# MCU.net
KiCad netlist of a schematic drawn in Altium Designer
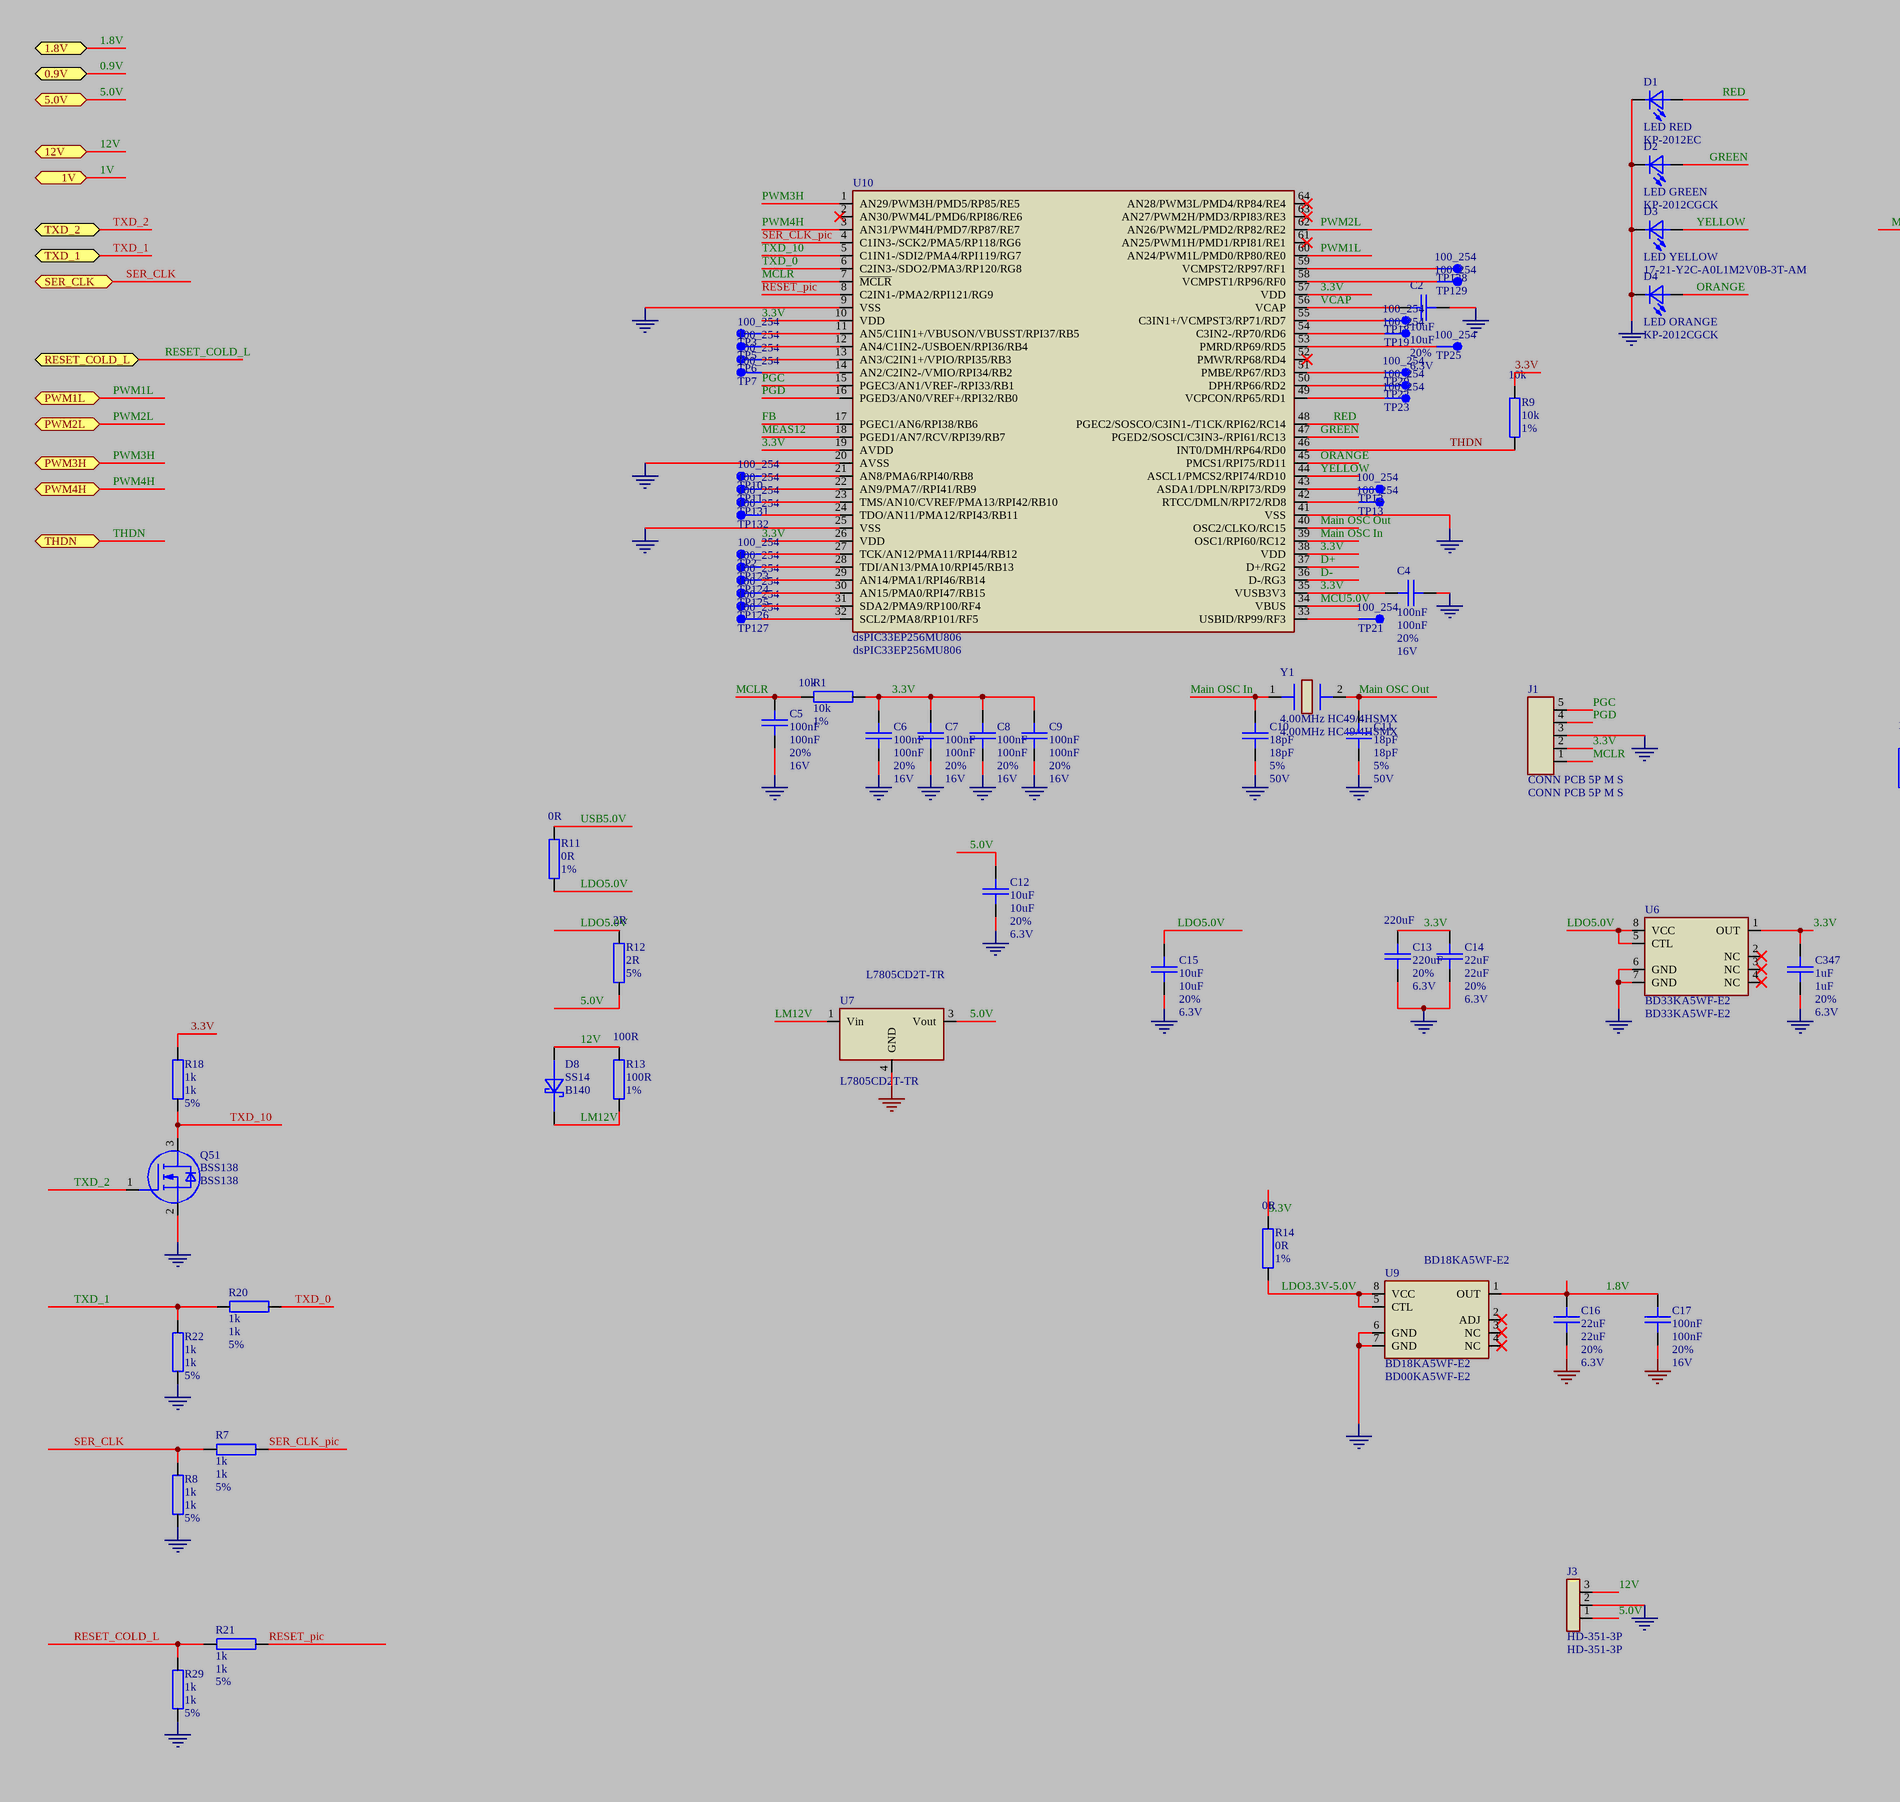
[diagram p0: MCU.SchDoc, left]
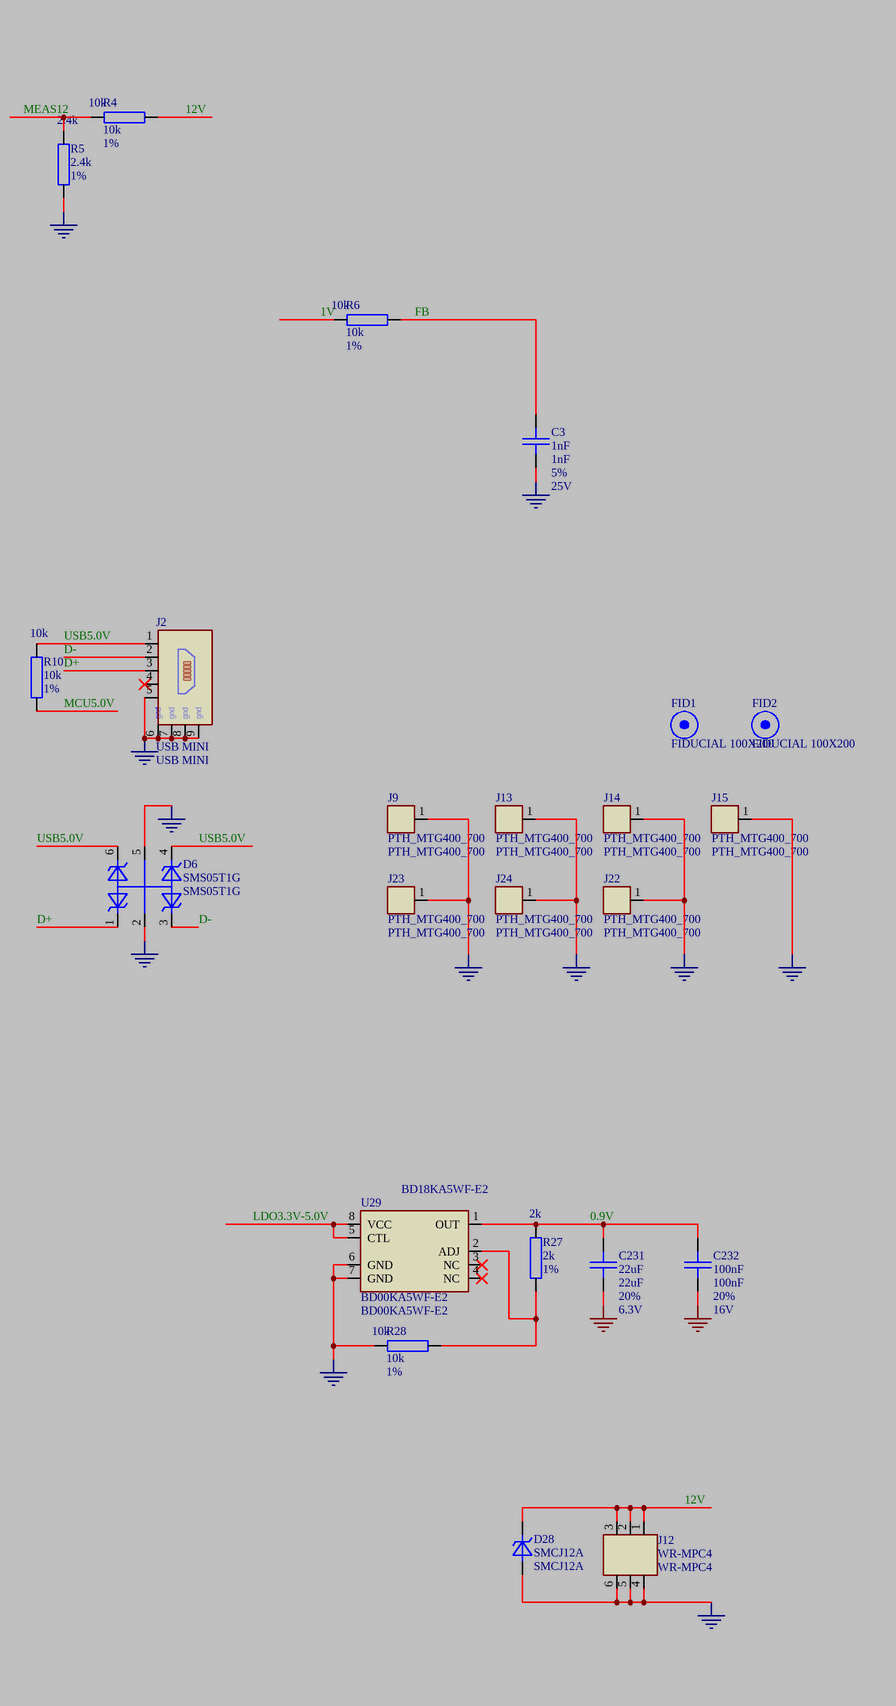
[diagram p1: MCU.SchDoc, right]

(export (version "E")
  (design (tool "Eeschema 10.0.6"))
  (components
    (comp (ref "C2")
      (value "10uF")
      (footprint "SMD_0603_CAPC1608X95N")
      (fields
        (field (name "DB_PART_NUMBER") "CAP000043646")
        (field (name "DB_VALUE") "10uF")
        (field (name "DB_TOLERANCE") "20%")
        (field (name "DB_VOLTAGE") "6.3V")
        (field (name "DB_MANUFACTURER_PART") "KEMET    C0603C106M9PAC")
        (field (name "DB_APPROVED_BY") "ISHIDDEN=T")
      )
      (libsource (lib "Database_Libs1") (part "C"))
    )
    (comp (ref "C3")
      (value "1nF")
      (footprint "SMD_0603_CAPC1608X95N")
      (fields
        (field (name "DB_PART_NUMBER") "CAP000024113")
        (field (name "DB_VALUE") "1nF")
        (field (name "DB_TOLERANCE") "5%")
        (field (name "DB_VOLTAGE") "25V")
        (field (name "DB_MANUFACTURER_PART") "KEMET    C0603C102J3RAC")
        (field (name "DB_APPROVED_BY") "ISHIDDEN=T")
      )
      (libsource (lib "Database_Libs1") (part "C"))
    )
    (comp (ref "C4")
      (value "100nF")
      (footprint "SMD_0402_CAPC1005X55N")
      (fields
        (field (name "DB_PART_NUMBER") "CAP000022751")
        (field (name "DB_VALUE") "100nF")
        (field (name "DB_TOLERANCE") "20%")
        (field (name "DB_VOLTAGE") "16V")
        (field (name "DB_MANUFACTURER_PART") "KEMET    C0402F104M4RAC")
        (field (name "DB_APPROVED_BY") "ISHIDDEN=T")
      )
      (libsource (lib "Database_Libs1") (part "C"))
    )
    (comp (ref "C5")
      (value "100nF")
      (footprint "SMD_0402_CAPC1005X55N")
      (fields
        (field (name "DB_PART_NUMBER") "CAP000022751")
        (field (name "DB_VALUE") "100nF")
        (field (name "DB_TOLERANCE") "20%")
        (field (name "DB_VOLTAGE") "16V")
        (field (name "DB_MANUFACTURER_PART") "KEMET    C0402F104M4RAC")
        (field (name "DB_APPROVED_BY") "ISHIDDEN=T")
      )
      (libsource (lib "Database_Libs1") (part "C"))
    )
    (comp (ref "C6")
      (value "100nF")
      (footprint "SMD_0402_CAPC1005X55N")
      (fields
        (field (name "DB_PART_NUMBER") "CAP000022751")
        (field (name "DB_VALUE") "100nF")
        (field (name "DB_TOLERANCE") "20%")
        (field (name "DB_VOLTAGE") "16V")
        (field (name "DB_MANUFACTURER_PART") "KEMET    C0402F104M4RAC")
        (field (name "DB_APPROVED_BY") "ISHIDDEN=T")
      )
      (libsource (lib "Database_Libs1") (part "C"))
    )
    (comp (ref "C7")
      (value "100nF")
      (footprint "SMD_0402_CAPC1005X55N")
      (fields
        (field (name "DB_PART_NUMBER") "CAP000022751")
        (field (name "DB_VALUE") "100nF")
        (field (name "DB_TOLERANCE") "20%")
        (field (name "DB_VOLTAGE") "16V")
        (field (name "DB_MANUFACTURER_PART") "KEMET    C0402F104M4RAC")
        (field (name "DB_APPROVED_BY") "ISHIDDEN=T")
      )
      (libsource (lib "Database_Libs1") (part "C"))
    )
    (comp (ref "C8")
      (value "100nF")
      (footprint "SMD_0402_CAPC1005X55N")
      (fields
        (field (name "DB_PART_NUMBER") "CAP000022751")
        (field (name "DB_VALUE") "100nF")
        (field (name "DB_TOLERANCE") "20%")
        (field (name "DB_VOLTAGE") "16V")
        (field (name "DB_MANUFACTURER_PART") "KEMET    C0402F104M4RAC")
        (field (name "DB_APPROVED_BY") "ISHIDDEN=T")
      )
      (libsource (lib "Database_Libs1") (part "C"))
    )
    (comp (ref "C9")
      (value "100nF")
      (footprint "SMD_0402_CAPC1005X55N")
      (fields
        (field (name "DB_PART_NUMBER") "CAP000022751")
        (field (name "DB_VALUE") "100nF")
        (field (name "DB_TOLERANCE") "20%")
        (field (name "DB_VOLTAGE") "16V")
        (field (name "DB_MANUFACTURER_PART") "KEMET    C0402F104M4RAC")
        (field (name "DB_APPROVED_BY") "ISHIDDEN=T")
      )
      (libsource (lib "Database_Libs1") (part "C"))
    )
    (comp (ref "C10")
      (value "18pF")
      (footprint "SMD_0603_CAPC1608X95N")
      (fields
        (field (name "DB_PART_NUMBER") "CAP000031922")
        (field (name "DB_VALUE") "18pF")
        (field (name "DB_TOLERANCE") "5%")
        (field (name "DB_VOLTAGE") "50V")
        (field (name "DB_MANUFACTURER_PART") "KEMET    C0603C180J5GAC")
        (field (name "DB_APPROVED_BY") "ISHIDDEN=T")
      )
      (libsource (lib "Database_Libs1") (part "C"))
    )
    (comp (ref "C11")
      (value "18pF")
      (footprint "SMD_0603_CAPC1608X95N")
      (fields
        (field (name "DB_PART_NUMBER") "CAP000031922")
        (field (name "DB_VALUE") "18pF")
        (field (name "DB_TOLERANCE") "5%")
        (field (name "DB_VOLTAGE") "50V")
        (field (name "DB_MANUFACTURER_PART") "KEMET    C0603C180J5GAC")
        (field (name "DB_APPROVED_BY") "ISHIDDEN=T")
      )
      (libsource (lib "Database_Libs1") (part "C"))
    )
    (comp (ref "C12")
      (value "10uF")
      (footprint "SMD_0603_CAPC1608X95N")
      (fields
        (field (name "DB_PART_NUMBER") "CAP000043646")
        (field (name "DB_VALUE") "10uF")
        (field (name "DB_TOLERANCE") "20%")
        (field (name "DB_VOLTAGE") "6.3V")
        (field (name "DB_MANUFACTURER_PART") "KEMET    C0603C106M9PAC")
        (field (name "DB_APPROVED_BY") "ISHIDDEN=T")
      )
      (libsource (lib "Database_Libs1") (part "C"))
    )
    (comp (ref "C13")
      (value "220uF")
      (footprint "SMD_1210_CAPC3225X279N")
      (fields
        (field (name "DB_PART_NUMBER") "CAP000047355")
        (field (name "DB_VALUE") "220uF")
        (field (name "DB_TOLERANCE") "20%")
        (field (name "DB_VOLTAGE") "6.3V")
        (field (name "DB_MANUFACTURER_PART") "SAMSUNG    CL32A227MQVNNNE")
        (field (name "DB_APPROVED_BY") "VSN")
      )
      (libsource (lib "Database_Libs1") (part "C"))
    )
    (comp (ref "C14")
      (value "22uF")
      (footprint "SMD_0805_CAPC2012X145N")
      (fields
        (field (name "DB_PART_NUMBER") "CAP000043686")
        (field (name "DB_VALUE") "22uF")
        (field (name "DB_TOLERANCE") "20%")
        (field (name "DB_VOLTAGE") "6.3V")
        (field (name "DB_MANUFACTURER_PART") "KEMET    C0805C226M9PAC")
        (field (name "DB_APPROVED_BY") "ISHIDDEN=T")
      )
      (libsource (lib "Database_Libs1") (part "C"))
    )
    (comp (ref "C15")
      (value "10uF")
      (footprint "SMD_0603_CAPC1608X95N")
      (fields
        (field (name "DB_PART_NUMBER") "CAP000043646")
        (field (name "DB_VALUE") "10uF")
        (field (name "DB_TOLERANCE") "20%")
        (field (name "DB_VOLTAGE") "6.3V")
        (field (name "DB_MANUFACTURER_PART") "KEMET    C0603C106M9PAC")
        (field (name "DB_APPROVED_BY") "ISHIDDEN=T")
      )
      (libsource (lib "Database_Libs1") (part "C"))
    )
    (comp (ref "C16")
      (value "22uF")
      (footprint "SMD_0805_CAPC2012X145N")
      (fields
        (field (name "DB_PART_NUMBER") "CAP000043686")
        (field (name "DB_VALUE") "22uF")
        (field (name "DB_TOLERANCE") "20%")
        (field (name "DB_VOLTAGE") "6.3V")
        (field (name "DB_MANUFACTURER_PART") "KEMET    C0805C226M9PAC")
        (field (name "DB_APPROVED_BY") "ISHIDDEN=T")
      )
      (libsource (lib "Database_Libs1") (part "C"))
    )
    (comp (ref "C17")
      (value "100nF")
      (footprint "SMD_0402_CAPC1005X55N")
      (fields
        (field (name "DB_PART_NUMBER") "CAP000022751")
        (field (name "DB_VALUE") "100nF")
        (field (name "DB_TOLERANCE") "20%")
        (field (name "DB_VOLTAGE") "16V")
        (field (name "DB_MANUFACTURER_PART") "KEMET    C0402F104M4RAC")
        (field (name "DB_APPROVED_BY") "ISHIDDEN=T")
      )
      (libsource (lib "Database_Libs1") (part "C"))
    )
    (comp (ref "C231")
      (value "22uF")
      (footprint "SMD_0805_CAPC2012X145N")
      (fields
        (field (name "DB_PART_NUMBER") "CAP000043686")
        (field (name "DB_VALUE") "22uF")
        (field (name "DB_TOLERANCE") "20%")
        (field (name "DB_VOLTAGE") "6.3V")
        (field (name "DB_MANUFACTURER_PART") "KEMET    C0805C226M9PAC")
        (field (name "DB_APPROVED_BY") "ISHIDDEN=T")
      )
      (libsource (lib "Database_Libs1") (part "C"))
    )
    (comp (ref "C232")
      (value "100nF")
      (footprint "SMD_0402_CAPC1005X55N")
      (fields
        (field (name "DB_PART_NUMBER") "CAP000022751")
        (field (name "DB_VALUE") "100nF")
        (field (name "DB_TOLERANCE") "20%")
        (field (name "DB_VOLTAGE") "16V")
        (field (name "DB_MANUFACTURER_PART") "KEMET    C0402F104M4RAC")
        (field (name "DB_APPROVED_BY") "ISHIDDEN=T")
      )
      (libsource (lib "Database_Libs1") (part "C"))
    )
    (comp (ref "C347")
      (value "1uF")
      (footprint "SMD_0603_CAPC1608X95N")
      (fields
        (field (name "DB_PART_NUMBER") "CAP000043344")
        (field (name "DB_VALUE") "1uF")
        (field (name "DB_TOLERANCE") "20%")
        (field (name "DB_VOLTAGE") "6.3V")
        (field (name "DB_MANUFACTURER_PART") "KEMET    C0603C105M9PAC")
        (field (name "DB_APPROVED_BY") "ISHIDDEN=T")
      )
      (libsource (lib "Database_Libs1") (part "C"))
    )
    (comp (ref "D1")
      (value "LED RED")
      (footprint "SMD_0805_LED2012X100N")
      (fields
        (field (name "DB_PART_NUMBER") "OPT000000095")
        (field (name "DB_VALUE") "KP-2012EC")
        (field (name "DB_MANUFACTURER_PART") "KINGBRIGHT       KP-2012EC")
        (field (name "DB_APPROVED_BY") "VSN")
      )
      (libsource (lib "Database_Libs1") (part "LED"))
    )
    (comp (ref "D2")
      (value "LED GREEN")
      (footprint "SMD_0805_LED2012X100N")
      (fields
        (field (name "DB_PART_NUMBER") "OPT000000096")
        (field (name "DB_VALUE") "KP-2012CGCK")
        (field (name "DB_MANUFACTURER_PART") "KINGBRIGHT       KP-2012CGCK")
        (field (name "DB_APPROVED_BY") "VSN")
      )
      (libsource (lib "Database_Libs1") (part "LED"))
    )
    (comp (ref "D3")
      (value "LED YELLOW")
      (footprint "SMD_0805_LED2012X100N")
      (fields
        (field (name "DB_PART_NUMBER") "OPT000000092")
        (field (name "DB_VALUE") "17-21-Y2C-A0L1M2V0B-3T-AM")
        (field (name "DB_MANUFACTURER_PART") "EVERLIGHT       17-21-Y2C-A0L1M2V0B-3T-AM")
        (field (name "DB_APPROVED_BY") "VSN")
      )
      (libsource (lib "Database_Libs1") (part "LED"))
    )
    (comp (ref "D4")
      (value "LED ORANGE")
      (footprint "SMD_0805_LED2012X100N")
      (fields
        (field (name "DB_PART_NUMBER") "OPT0000000zz")
        (field (name "DB_VALUE") "KP-2012CGCK")
        (field (name "DB_MANUFACTURER_PART") "KINGBRIGHT       KP-2012CGCK")
        (field (name "DB_APPROVED_BY") "VSN")
      )
      (libsource (lib "Database_Libs1") (part "LED"))
    )
    (comp (ref "D6")
      (value "SMS05T1G")
      (footprint "SMD_SOT457_SOT95P275X110-6N")
      (fields
        (field (name "DB_PART_NUMBER") "DDE000002846")
        (field (name "DB_VALUE") "SMS05T1G")
        (field (name "DB_MANUFACTURER_PART") "ON SEMICONDUCTOR        SMS05T1G")
        (field (name "DB_APPROVED_BY") "VSN")
      )
      (libsource (lib "Database_Libs1") (part "D_TVS_QUAD_C1A2C3C4A5C6"))
    )
    (comp (ref "D8")
      (value "SS14")
      (footprint "SMD_DO214AC_SMA")
      (fields
        (field (name "DB_PART_NUMBER") "DDE000000580")
        (field (name "DB_VALUE") "B140")
        (field (name "DB_MANUFACTURER_PART") "Diodes        B140")
        (field (name "DB_APPROVED_BY") "ISHIDDEN=T")
      )
      (libsource (lib "Database_Libs1") (part "D_STKY"))
    )
    (comp (ref "D28")
      (value "SMCJ12A")
      (footprint "SMD_DO214AC_SMC")
      (fields
        (field (name "DB_PART_NUMBER") "DDE000001725")
        (field (name "DB_VALUE") "SMCJ12A")
        (field (name "DB_MANUFACTURER_PART") "Diodes        SMCJ12A")
        (field (name "DB_APPROVED_BY") "ISHIDDEN=T")
      )
      (libsource (lib "Database_Libs1") (part "D_TVS_UNI"))
    )
    (comp (ref "FID1")
      (value "FIDUCIAL 100X200")
      (footprint "FID100X200")
      (fields
        (field (name "DB_PART_NUMBER") "FID000000001")
        (field (name "DB_MANUFACTURER_PART") "ISHIDDEN=T")
        (field (name "DB_APPROVED_BY") "ISHIDDEN=T")
      )
      (libsource (lib "Database_Libs1") (part "FIDUCIAL"))
    )
    (comp (ref "FID2")
      (value "FIDUCIAL 100X200")
      (footprint "FID100X200")
      (fields
        (field (name "DB_PART_NUMBER") "FID000000001")
        (field (name "DB_MANUFACTURER_PART") "ISHIDDEN=T")
        (field (name "DB_APPROVED_BY") "ISHIDDEN=T")
      )
      (libsource (lib "Database_Libs1") (part "FIDUCIAL"))
    )
    (comp (ref "J1")
      (value "CONN PCB 5P M S")
      (footprint "PTH_HDRV05W64P254_1X05")
      (fields
        (field (name "DB_PART_NUMBER") "CON000000006")
        (field (name "DB_VALUE") "CONN PCB 5P M S")
        (field (name "DB_MANUFACTURER_PART") "W+P        143-12-005-00")
        (field (name "DB_APPROVED_BY") "VSN")
      )
      (libsource (lib "Database_Libs1") (part "CON_5PINS"))
    )
    (comp (ref "J2")
      (value "USB MINI")
      (footprint "SMD_CON-CVILUX-CU04-SCM15B0")
      (fields
        (field (name "DB_PART_NUMBER") "CON000000048")
        (field (name "DB_VALUE") "USB MINI")
        (field (name "DB_MANUFACTURER_PART") "CVILUX       CU04-SCM15B0-R0-LF")
        (field (name "DB_APPROVED_BY") "VSN")
      )
      (libsource (lib "Database_Libs1") (part "CON_USB_MINI_1"))
    )
    (comp (ref "J3")
      (value "HD-351-3P")
      (footprint "PTH_CON_HD-351-3P")
      (fields
        (field (name "DB_PART_NUMBER") "CON000000272")
        (field (name "DB_VALUE") "HD-351-3P")
        (field (name "DB_MANUFACTURER_PART") "HOW DER      HD-351-3P")
        (field (name "DB_APPROVED_BY") "VSN")
      )
      (libsource (lib "Database_Libs1") (part "CON_3PINS"))
    )
    (comp (ref "J9")
      (value "PTH_MTG400_700")
      (footprint "PTH_MTG400_700")
      (fields
        (field (name "DB_PART_NUMBER") "MTH000000030")
        (field (name "DB_VALUE") "PTH_MTG400_700")
        (field (name "DB_APPROVED_BY") "VSN")
      )
      (libsource (lib "Database_Libs1") (part "CON_1PIN"))
    )
    (comp (ref "J12")
      (value "WR-MPC4")
      (footprint "PTH_CON_WR-MRC4-6P_S")
      (fields
        (field (name "DB_PART_NUMBER") "CON000000279")
        (field (name "DB_VALUE") "WR-MPC4")
        (field (name "DB_MANUFACTURER_PART") "WE        	649 006 211 22")
        (field (name "DB_APPROVED_BY") "VSN")
      )
      (libsource (lib "Database_Libs1") (part "CON_2ROWS_6PINS_1"))
    )
    (comp (ref "J13")
      (value "PTH_MTG400_700")
      (footprint "PTH_MTG400_700")
      (fields
        (field (name "DB_PART_NUMBER") "MTH000000030")
        (field (name "DB_VALUE") "PTH_MTG400_700")
        (field (name "DB_APPROVED_BY") "VSN")
      )
      (libsource (lib "Database_Libs1") (part "CON_1PIN"))
    )
    (comp (ref "J14")
      (value "PTH_MTG400_700")
      (footprint "PTH_MTG400_700")
      (fields
        (field (name "DB_PART_NUMBER") "MTH000000030")
        (field (name "DB_VALUE") "PTH_MTG400_700")
        (field (name "DB_APPROVED_BY") "VSN")
      )
      (libsource (lib "Database_Libs1") (part "CON_1PIN"))
    )
    (comp (ref "J15")
      (value "PTH_MTG400_700")
      (footprint "PTH_MTG400_700")
      (fields
        (field (name "DB_PART_NUMBER") "MTH000000030")
        (field (name "DB_VALUE") "PTH_MTG400_700")
        (field (name "DB_APPROVED_BY") "VSN")
      )
      (libsource (lib "Database_Libs1") (part "CON_1PIN"))
    )
    (comp (ref "J22")
      (value "PTH_MTG400_700")
      (footprint "PTH_MTG400_700")
      (fields
        (field (name "DB_PART_NUMBER") "MTH000000030")
        (field (name "DB_VALUE") "PTH_MTG400_700")
        (field (name "DB_APPROVED_BY") "VSN")
      )
      (libsource (lib "Database_Libs1") (part "CON_1PIN"))
    )
    (comp (ref "J23")
      (value "PTH_MTG400_700")
      (footprint "PTH_MTG400_700")
      (fields
        (field (name "DB_PART_NUMBER") "MTH000000030")
        (field (name "DB_VALUE") "PTH_MTG400_700")
        (field (name "DB_APPROVED_BY") "VSN")
      )
      (libsource (lib "Database_Libs1") (part "CON_1PIN"))
    )
    (comp (ref "J24")
      (value "PTH_MTG400_700")
      (footprint "PTH_MTG400_700")
      (fields
        (field (name "DB_PART_NUMBER") "MTH000000030")
        (field (name "DB_VALUE") "PTH_MTG400_700")
        (field (name "DB_APPROVED_BY") "VSN")
      )
      (libsource (lib "Database_Libs1") (part "CON_1PIN"))
    )
    (comp (ref "Q51")
      (value "BSS138")
      (footprint "SMD_SOT23_SOT95P240X112-3N")
      (fields
        (field (name "DB_PART_NUMBER") "TRA000001460")
        (field (name "DB_VALUE") "BSS138")
        (field (name "DB_MANUFACTURER_PART") "FAIRCHILD        BSS138LT1G")
        (field (name "DB_APPROVED_BY") "VSN")
      )
      (libsource (lib "Database_Libs1") (part "MOS_N_D1_G1S2D3"))
    )
    (comp (ref "R1")
      (value "10k")
      (footprint "SMD_0603_RESC1608X55N")
      (fields
        (field (name "DB_PART_NUMBER") "RES000008663")
        (field (name "DB_VALUE") "10k")
        (field (name "DB_TOLERANCE") "1%")
        (field (name "DB_MANUFACTURER_PART") "YAGEO    RC0603FR-0710KL")
        (field (name "DB_APPROVED_BY") "VSN")
      )
      (libsource (lib "Database_Libs1") (part "R"))
    )
    (comp (ref "R4")
      (value "10k")
      (footprint "SMD_0603_RESC1608X55N")
      (fields
        (field (name "DB_PART_NUMBER") "RES000008663")
        (field (name "DB_VALUE") "10k")
        (field (name "DB_TOLERANCE") "1%")
        (field (name "DB_MANUFACTURER_PART") "YAGEO    RC0603FR-0710KL")
        (field (name "DB_APPROVED_BY") "VSN")
      )
      (libsource (lib "Database_Libs1") (part "R"))
    )
    (comp (ref "R5")
      (value "2.4k")
      (footprint "SMD_0603_RESC1608X55N")
      (fields
        (field (name "DB_PART_NUMBER") "RES000006261")
        (field (name "DB_VALUE") "2.4k")
        (field (name "DB_TOLERANCE") "1%")
        (field (name "DB_MANUFACTURER_PART") "YAGEO    RC0603FR-072K4")
        (field (name "DB_APPROVED_BY") "ISHIDDEN=T")
      )
      (libsource (lib "Database_Libs1") (part "R"))
    )
    (comp (ref "R6")
      (value "10k")
      (footprint "SMD_0603_RESC1608X55N")
      (fields
        (field (name "DB_PART_NUMBER") "RES000008663")
        (field (name "DB_VALUE") "10k")
        (field (name "DB_TOLERANCE") "1%")
        (field (name "DB_MANUFACTURER_PART") "YAGEO    RC0603FR-0710KL")
        (field (name "DB_APPROVED_BY") "VSN")
      )
      (libsource (lib "Database_Libs1") (part "R"))
    )
    (comp (ref "R7")
      (value "1k")
      (footprint "SMD_0603_RESC1608X55N")
      (fields
        (field (name "DB_PART_NUMBER") "RES000008858")
        (field (name "DB_VALUE") "1k")
        (field (name "DB_TOLERANCE") "5%")
        (field (name "DB_MANUFACTURER_PART") "YAGEO    AC0603JR-071KL")
        (field (name "DB_APPROVED_BY") "VSN")
      )
      (libsource (lib "Database_Libs1") (part "R"))
    )
    (comp (ref "R8")
      (value "1k")
      (footprint "SMD_0603_RESC1608X55N")
      (fields
        (field (name "DB_PART_NUMBER") "RES000008858")
        (field (name "DB_VALUE") "1k")
        (field (name "DB_TOLERANCE") "5%")
        (field (name "DB_MANUFACTURER_PART") "YAGEO    AC0603JR-071KL")
        (field (name "DB_APPROVED_BY") "VSN")
      )
      (libsource (lib "Database_Libs1") (part "R"))
    )
    (comp (ref "R9")
      (value "10k")
      (footprint "SMD_0603_RESC1608X55N")
      (fields
        (field (name "DB_PART_NUMBER") "RES000008663")
        (field (name "DB_VALUE") "10k")
        (field (name "DB_TOLERANCE") "1%")
        (field (name "DB_MANUFACTURER_PART") "YAGEO    RC0603FR-0710KL")
        (field (name "DB_APPROVED_BY") "VSN")
      )
      (libsource (lib "Database_Libs1") (part "R"))
    )
    (comp (ref "R10")
      (value "10k")
      (footprint "SMD_0603_RESC1608X55N")
      (fields
        (field (name "DB_PART_NUMBER") "RES000008663")
        (field (name "DB_VALUE") "10k")
        (field (name "DB_TOLERANCE") "1%")
        (field (name "DB_MANUFACTURER_PART") "YAGEO    RC0603FR-0710KL")
        (field (name "DB_APPROVED_BY") "VSN")
      )
      (libsource (lib "Database_Libs1") (part "R"))
    )
    (comp (ref "R11")
      (value "0R")
      (footprint "SMD_0603_RESC1608X55N")
      (fields
        (field (name "DB_PART_NUMBER") "RES000008926")
        (field (name "DB_VALUE") "0R")
        (field (name "DB_TOLERANCE") "1%")
        (field (name "DB_MANUFACTURER_PART") "YAGEO    AC0603FR-070RL")
        (field (name "DB_APPROVED_BY") "VSN")
      )
      (libsource (lib "Database_Libs1") (part "R"))
    )
    (comp (ref "R12")
      (value "2R")
      (footprint "SMD_1206_RESC3216X65N")
      (fields
        (field (name "DB_PART_NUMBER") "RES000007051")
        (field (name "DB_VALUE") "2R")
        (field (name "DB_TOLERANCE") "5%")
        (field (name "DB_MANUFACTURER_PART") "YAGEO    RC1206JR-072R")
        (field (name "DB_APPROVED_BY") "ISHIDDEN=T")
      )
      (libsource (lib "Database_Libs1") (part "R"))
    )
    (comp (ref "R13")
      (value "100R")
      (footprint "SMD_1206_RESC3216X65N")
      (fields
        (field (name "DB_PART_NUMBER") "RES000006922")
        (field (name "DB_VALUE") "100R")
        (field (name "DB_TOLERANCE") "1%")
        (field (name "DB_MANUFACTURER_PART") "YAGEO    RC1206FR-07100R")
        (field (name "DB_APPROVED_BY") "ISHIDDEN=T")
      )
      (libsource (lib "Database_Libs1") (part "R"))
    )
    (comp (ref "R14")
      (value "0R")
      (footprint "SMD_1206_RESC3216X65N")
      (fields
        (field (name "DB_PART_NUMBER") "RES000008756")
        (field (name "DB_VALUE") "0R")
        (field (name "DB_TOLERANCE") "1%")
        (field (name "DB_MANUFACTURER_PART") "YAGEO    AC1206FR-070RL")
        (field (name "DB_APPROVED_BY") "VSN")
      )
      (libsource (lib "Database_Libs1") (part "R"))
    )
    (comp (ref "R18")
      (value "1k")
      (footprint "SMD_0603_RESC1608X55N")
      (fields
        (field (name "DB_PART_NUMBER") "RES000008858")
        (field (name "DB_VALUE") "1k")
        (field (name "DB_TOLERANCE") "5%")
        (field (name "DB_MANUFACTURER_PART") "YAGEO    AC0603JR-071KL")
        (field (name "DB_APPROVED_BY") "VSN")
      )
      (libsource (lib "Database_Libs1") (part "R"))
    )
    (comp (ref "R20")
      (value "1k")
      (footprint "SMD_0603_RESC1608X55N")
      (fields
        (field (name "DB_PART_NUMBER") "RES000008858")
        (field (name "DB_VALUE") "1k")
        (field (name "DB_TOLERANCE") "5%")
        (field (name "DB_MANUFACTURER_PART") "YAGEO    AC0603JR-071KL")
        (field (name "DB_APPROVED_BY") "VSN")
      )
      (libsource (lib "Database_Libs1") (part "R"))
    )
    (comp (ref "R21")
      (value "1k")
      (footprint "SMD_0603_RESC1608X55N")
      (fields
        (field (name "DB_PART_NUMBER") "RES000008858")
        (field (name "DB_VALUE") "1k")
        (field (name "DB_TOLERANCE") "5%")
        (field (name "DB_MANUFACTURER_PART") "YAGEO    AC0603JR-071KL")
        (field (name "DB_APPROVED_BY") "VSN")
      )
      (libsource (lib "Database_Libs1") (part "R"))
    )
    (comp (ref "R22")
      (value "1k")
      (footprint "SMD_0603_RESC1608X55N")
      (fields
        (field (name "DB_PART_NUMBER") "RES000008858")
        (field (name "DB_VALUE") "1k")
        (field (name "DB_TOLERANCE") "5%")
        (field (name "DB_MANUFACTURER_PART") "YAGEO    AC0603JR-071KL")
        (field (name "DB_APPROVED_BY") "VSN")
      )
      (libsource (lib "Database_Libs1") (part "R"))
    )
    (comp (ref "R27")
      (value "2k")
      (footprint "SMD_0603_RESC1608X55N")
      (fields
        (field (name "DB_PART_NUMBER") "RES000006259")
        (field (name "DB_VALUE") "2k")
        (field (name "DB_TOLERANCE") "1%")
        (field (name "DB_MANUFACTURER_PART") "YAGEO    RC0603FR-072K")
        (field (name "DB_APPROVED_BY") "ISHIDDEN=T")
      )
      (libsource (lib "Database_Libs1") (part "R"))
    )
    (comp (ref "R28")
      (value "10k")
      (footprint "SMD_0603_RESC1608X55N")
      (fields
        (field (name "DB_PART_NUMBER") "RES000006276")
        (field (name "DB_VALUE") "10k")
        (field (name "DB_TOLERANCE") "1%")
        (field (name "DB_MANUFACTURER_PART") "YAGEO    RC0603FR-0710K")
        (field (name "DB_APPROVED_BY") "ISHIDDEN=T")
      )
      (libsource (lib "Database_Libs1") (part "R"))
    )
    (comp (ref "R29")
      (value "1k")
      (footprint "SMD_0603_RESC1608X55N")
      (fields
        (field (name "DB_PART_NUMBER") "RES000008858")
        (field (name "DB_VALUE") "1k")
        (field (name "DB_TOLERANCE") "5%")
        (field (name "DB_MANUFACTURER_PART") "YAGEO    AC0603JR-071KL")
        (field (name "DB_APPROVED_BY") "VSN")
      )
      (libsource (lib "Database_Libs1") (part "R"))
    )
    (comp (ref "TP2")
      (value "100_254")
      (footprint "SMD_TP_100-254")
      (fields
        (field (name "DB_PART_NUMBER") "TPO000000001")
        (field (name "DB_MANUFACTURER_PART") "ISHIDDEN=T")
        (field (name "DB_APPROVED_BY") "ISHIDDEN=T")
      )
      (libsource (lib "Database_Libs1") (part "TEST_POINT_1"))
    )
    (comp (ref "TP3")
      (value "100_254")
      (footprint "SMD_TP_100-254")
      (fields
        (field (name "DB_PART_NUMBER") "TPO000000001")
        (field (name "DB_MANUFACTURER_PART") "ISHIDDEN=T")
        (field (name "DB_APPROVED_BY") "ISHIDDEN=T")
      )
      (libsource (lib "Database_Libs1") (part "TEST_POINT_1"))
    )
    (comp (ref "TP5")
      (value "100_254")
      (footprint "SMD_TP_100-254")
      (fields
        (field (name "DB_PART_NUMBER") "TPO000000001")
        (field (name "DB_MANUFACTURER_PART") "ISHIDDEN=T")
        (field (name "DB_APPROVED_BY") "ISHIDDEN=T")
      )
      (libsource (lib "Database_Libs1") (part "TEST_POINT_1"))
    )
    (comp (ref "TP6")
      (value "100_254")
      (footprint "SMD_TP_100-254")
      (fields
        (field (name "DB_PART_NUMBER") "TPO000000001")
        (field (name "DB_MANUFACTURER_PART") "ISHIDDEN=T")
        (field (name "DB_APPROVED_BY") "ISHIDDEN=T")
      )
      (libsource (lib "Database_Libs1") (part "TEST_POINT_1"))
    )
    (comp (ref "TP7")
      (value "100_254")
      (footprint "SMD_TP_100-254")
      (fields
        (field (name "DB_PART_NUMBER") "TPO000000001")
        (field (name "DB_MANUFACTURER_PART") "ISHIDDEN=T")
        (field (name "DB_APPROVED_BY") "ISHIDDEN=T")
      )
      (libsource (lib "Database_Libs1") (part "TEST_POINT_1"))
    )
    (comp (ref "TP10")
      (value "100_254")
      (footprint "SMD_TP_100-254")
      (fields
        (field (name "DB_PART_NUMBER") "TPO000000001")
        (field (name "DB_MANUFACTURER_PART") "ISHIDDEN=T")
        (field (name "DB_APPROVED_BY") "ISHIDDEN=T")
      )
      (libsource (lib "Database_Libs1") (part "TEST_POINT_1"))
    )
    (comp (ref "TP11")
      (value "100_254")
      (footprint "SMD_TP_100-254")
      (fields
        (field (name "DB_PART_NUMBER") "TPO000000001")
        (field (name "DB_MANUFACTURER_PART") "ISHIDDEN=T")
        (field (name "DB_APPROVED_BY") "ISHIDDEN=T")
      )
      (libsource (lib "Database_Libs1") (part "TEST_POINT_1"))
    )
    (comp (ref "TP12")
      (value "100_254")
      (footprint "SMD_TP_100-254")
      (fields
        (field (name "DB_PART_NUMBER") "TPO000000001")
        (field (name "DB_MANUFACTURER_PART") "ISHIDDEN=T")
        (field (name "DB_APPROVED_BY") "ISHIDDEN=T")
      )
      (libsource (lib "Database_Libs1") (part "TEST_POINT_1"))
    )
    (comp (ref "TP13")
      (value "100_254")
      (footprint "SMD_TP_100-254")
      (fields
        (field (name "DB_PART_NUMBER") "TPO000000001")
        (field (name "DB_MANUFACTURER_PART") "ISHIDDEN=T")
        (field (name "DB_APPROVED_BY") "ISHIDDEN=T")
      )
      (libsource (lib "Database_Libs1") (part "TEST_POINT_1"))
    )
    (comp (ref "TP18")
      (value "100_254")
      (footprint "SMD_TP_100-254")
      (fields
        (field (name "DB_PART_NUMBER") "TPO000000001")
        (field (name "DB_MANUFACTURER_PART") "ISHIDDEN=T")
        (field (name "DB_APPROVED_BY") "ISHIDDEN=T")
      )
      (libsource (lib "Database_Libs1") (part "TEST_POINT_1"))
    )
    (comp (ref "TP19")
      (value "100_254")
      (footprint "SMD_TP_100-254")
      (fields
        (field (name "DB_PART_NUMBER") "TPO000000001")
        (field (name "DB_MANUFACTURER_PART") "ISHIDDEN=T")
        (field (name "DB_APPROVED_BY") "ISHIDDEN=T")
      )
      (libsource (lib "Database_Libs1") (part "TEST_POINT_1"))
    )
    (comp (ref "TP20")
      (value "100_254")
      (footprint "SMD_TP_100-254")
      (fields
        (field (name "DB_PART_NUMBER") "TPO000000001")
        (field (name "DB_MANUFACTURER_PART") "ISHIDDEN=T")
        (field (name "DB_APPROVED_BY") "ISHIDDEN=T")
      )
      (libsource (lib "Database_Libs1") (part "TEST_POINT_1"))
    )
    (comp (ref "TP21")
      (value "100_254")
      (footprint "SMD_TP_100-254")
      (fields
        (field (name "DB_PART_NUMBER") "TPO000000001")
        (field (name "DB_MANUFACTURER_PART") "ISHIDDEN=T")
        (field (name "DB_APPROVED_BY") "ISHIDDEN=T")
      )
      (libsource (lib "Database_Libs1") (part "TEST_POINT_1"))
    )
    (comp (ref "TP22")
      (value "100_254")
      (footprint "SMD_TP_100-254")
      (fields
        (field (name "DB_PART_NUMBER") "TPO000000001")
        (field (name "DB_MANUFACTURER_PART") "ISHIDDEN=T")
        (field (name "DB_APPROVED_BY") "ISHIDDEN=T")
      )
      (libsource (lib "Database_Libs1") (part "TEST_POINT_1"))
    )
    (comp (ref "TP23")
      (value "100_254")
      (footprint "SMD_TP_100-254")
      (fields
        (field (name "DB_PART_NUMBER") "TPO000000001")
        (field (name "DB_MANUFACTURER_PART") "ISHIDDEN=T")
        (field (name "DB_APPROVED_BY") "ISHIDDEN=T")
      )
      (libsource (lib "Database_Libs1") (part "TEST_POINT_1"))
    )
    (comp (ref "TP25")
      (value "100_254")
      (footprint "SMD_TP_100-254")
      (fields
        (field (name "DB_PART_NUMBER") "TPO000000001")
        (field (name "DB_MANUFACTURER_PART") "ISHIDDEN=T")
        (field (name "DB_APPROVED_BY") "ISHIDDEN=T")
      )
      (libsource (lib "Database_Libs1") (part "TEST_POINT_1"))
    )
    (comp (ref "TP123")
      (value "100_254")
      (footprint "SMD_TP_100-254")
      (fields
        (field (name "DB_PART_NUMBER") "TPO000000001")
        (field (name "DB_MANUFACTURER_PART") "ISHIDDEN=T")
        (field (name "DB_APPROVED_BY") "ISHIDDEN=T")
      )
      (libsource (lib "Database_Libs1") (part "TEST_POINT_1"))
    )
    (comp (ref "TP124")
      (value "100_254")
      (footprint "SMD_TP_100-254")
      (fields
        (field (name "DB_PART_NUMBER") "TPO000000001")
        (field (name "DB_MANUFACTURER_PART") "ISHIDDEN=T")
        (field (name "DB_APPROVED_BY") "ISHIDDEN=T")
      )
      (libsource (lib "Database_Libs1") (part "TEST_POINT_1"))
    )
    (comp (ref "TP125")
      (value "100_254")
      (footprint "SMD_TP_100-254")
      (fields
        (field (name "DB_PART_NUMBER") "TPO000000001")
        (field (name "DB_MANUFACTURER_PART") "ISHIDDEN=T")
        (field (name "DB_APPROVED_BY") "ISHIDDEN=T")
      )
      (libsource (lib "Database_Libs1") (part "TEST_POINT_1"))
    )
    (comp (ref "TP126")
      (value "100_254")
      (footprint "SMD_TP_100-254")
      (fields
        (field (name "DB_PART_NUMBER") "TPO000000001")
        (field (name "DB_MANUFACTURER_PART") "ISHIDDEN=T")
        (field (name "DB_APPROVED_BY") "ISHIDDEN=T")
      )
      (libsource (lib "Database_Libs1") (part "TEST_POINT_1"))
    )
    (comp (ref "TP127")
      (value "100_254")
      (footprint "SMD_TP_100-254")
      (fields
        (field (name "DB_PART_NUMBER") "TPO000000001")
        (field (name "DB_MANUFACTURER_PART") "ISHIDDEN=T")
        (field (name "DB_APPROVED_BY") "ISHIDDEN=T")
      )
      (libsource (lib "Database_Libs1") (part "TEST_POINT_1"))
    )
    (comp (ref "TP128")
      (value "100_254")
      (footprint "SMD_TP_100-254")
      (fields
        (field (name "DB_PART_NUMBER") "TPO000000001")
        (field (name "DB_MANUFACTURER_PART") "ISHIDDEN=T")
        (field (name "DB_APPROVED_BY") "ISHIDDEN=T")
      )
      (libsource (lib "Database_Libs1") (part "TEST_POINT_1"))
    )
    (comp (ref "TP129")
      (value "100_254")
      (footprint "SMD_TP_100-254")
      (fields
        (field (name "DB_PART_NUMBER") "TPO000000001")
        (field (name "DB_MANUFACTURER_PART") "ISHIDDEN=T")
        (field (name "DB_APPROVED_BY") "ISHIDDEN=T")
      )
      (libsource (lib "Database_Libs1") (part "TEST_POINT_1"))
    )
    (comp (ref "TP131")
      (value "100_254")
      (footprint "SMD_TP_100-254")
      (fields
        (field (name "DB_PART_NUMBER") "TPO000000001")
        (field (name "DB_MANUFACTURER_PART") "ISHIDDEN=T")
        (field (name "DB_APPROVED_BY") "ISHIDDEN=T")
      )
      (libsource (lib "Database_Libs1") (part "TEST_POINT_1"))
    )
    (comp (ref "TP132")
      (value "100_254")
      (footprint "SMD_TP_100-254")
      (fields
        (field (name "DB_PART_NUMBER") "TPO000000001")
        (field (name "DB_MANUFACTURER_PART") "ISHIDDEN=T")
        (field (name "DB_APPROVED_BY") "ISHIDDEN=T")
      )
      (libsource (lib "Database_Libs1") (part "TEST_POINT_1"))
    )
    (comp (ref "U6")
      (value "BD33KA5WF-E2")
      (footprint "SMD_SOIC127P620X160-8N")
      (fields
        (field (name "DB_PART_NUMBER") "PSU000000127")
        (field (name "DB_VALUE") "BD33KA5WF-E2")
        (field (name "DB_MANUFACTURER_PART") "ROHM        BD33KA5WF-E2")
        (field (name "DB_APPROVED_BY") "VSN")
      )
      (libsource (lib "Database_Libs1") (part "IC_BDXXKA5WF"))
    )
    (comp (ref "U7")
      (value "L7805CD2T-TR")
      (footprint "SMD_TO254P1542X460-3_4N")
      (fields
        (field (name "DB_PART_NUMBER") "PSU000000129")
        (field (name "DB_VALUE") "L7805CD2T-TR")
        (field (name "DB_MANUFACTURER_PART") "ST       L7805CD2T-TR")
        (field (name "DB_APPROVED_BY") "VSN")
      )
      (libsource (lib "Database_Libs1") (part "IC_IN1OUT3GND4"))
    )
    (comp (ref "U9")
      (value "BD18KA5WF-E2")
      (footprint "SMD_SOIC127P620X160-8N")
      (fields
        (field (name "DB_PART_NUMBER") "PSU000000128")
        (field (name "DB_VALUE") "BD00KA5WF-E2")
        (field (name "DB_MANUFACTURER_PART") "ROHM        BD00KA5WF-E2")
        (field (name "DB_APPROVED_BY") "VSN")
      )
      (libsource (lib "Database_Libs1") (part "IC_BD00KA5WF"))
    )
    (comp (ref "U10")
      (value "dsPIC33EP256MU806")
      (footprint "SMD_QFP50P1200X1200X120-64N")
      (fields
        (field (name "DB_PART_NUMBER") "MCU000000070")
        (field (name "DB_VALUE") "dsPIC33EP256MU806")
        (field (name "DB_MANUFACTURER_PART") "MICROCHIP        DSPIC33EP256MU806-E/PT")
        (field (name "DB_APPROVED_BY") "VSN")
      )
      (libsource (lib "Database_Libs1") (part "IC_DSPIC33EP256MU806-QFN64"))
    )
    (comp (ref "U29")
      (value "BD00KA5WF-E2")
      (footprint "SMD_SOIC127P620X160-8N")
      (fields
        (field (name "DB_PART_NUMBER") "PSU000000128")
        (field (name "DB_VALUE") "BD00KA5WF-E2")
        (field (name "DB_MANUFACTURER_PART") "ROHM        BD00KA5WF-E2")
        (field (name "DB_APPROVED_BY") "VSN")
      )
      (libsource (lib "Database_Libs1") (part "IC_BD00KA5WF"))
    )
    (comp (ref "Y1")
      (value "4.00MHz HC49/4HSMX")
      (footprint "SMD_HC49_XTAL1140X480X420N")
      (fields
        (field (name "DB_PART_NUMBER") "OSC000000012")
        (field (name "DB_VALUE") "4.00MHz HC49/4HSMX")
        (field (name "DB_MANUFACTURER_PART") "IQD       4.00MHz HC49/4HSMX")
        (field (name "DB_APPROVED_BY") "VSN")
      )
      (libsource (lib "Database_Libs1") (part "XTAL"))
    )
  )
  (nets
    (net (code "1") (name "/0.9V") (class "Default")
      (node (ref "C231") (pin "1") (pinfunction "1_1") (pintype "passive"))
      (node (ref "C232") (pin "1") (pinfunction "1_1") (pintype "passive"))
      (node (ref "R27") (pin "1") (pinfunction "1_1") (pintype "passive"))
      (node (ref "U29") (pin "1") (pinfunction "OUT_1") (pintype "passive"))
    )
    (net (code "2") (name "/1.8V") (class "Default")
      (node (ref "C16") (pin "1") (pinfunction "1_1") (pintype "passive"))
      (node (ref "C17") (pin "1") (pinfunction "1_1") (pintype "passive"))
      (node (ref "U9") (pin "1") (pinfunction "OUT_1") (pintype "passive"))
    )
    (net (code "3") (name "/1V") (class "Default")
      (node (ref "R6") (pin "2") (pinfunction "2_2") (pintype "passive"))
    )
    (net (code "4") (name "/3.3V") (class "Default")
      (node (ref "C13") (pin "2") (pinfunction "2_2") (pintype "passive"))
      (node (ref "C14") (pin "1") (pinfunction "1_1") (pintype "passive"))
      (node (ref "C347") (pin "1") (pinfunction "1_1") (pintype "passive"))
      (node (ref "C4") (pin "1") (pinfunction "1_1") (pintype "passive"))
      (node (ref "C6") (pin "1") (pinfunction "1_1") (pintype "passive"))
      (node (ref "C7") (pin "1") (pinfunction "1_1") (pintype "passive"))
      (node (ref "C8") (pin "1") (pinfunction "1_1") (pintype "passive"))
      (node (ref "C9") (pin "1") (pinfunction "1_1") (pintype "passive"))
      (node (ref "J1") (pin "2") (pinfunction "2_2") (pintype "passive"))
      (node (ref "R1") (pin "2") (pinfunction "2_2") (pintype "passive"))
      (node (ref "R14") (pin "2") (pinfunction "2_2") (pintype "passive"))
      (node (ref "R18") (pin "1") (pinfunction "1_1") (pintype "passive"))
      (node (ref "R9") (pin "2") (pinfunction "2_2") (pintype "passive"))
      (node (ref "U10") (pin "10") (pinfunction "VDD_10") (pintype "passive"))
      (node (ref "U10") (pin "19") (pinfunction "AVDD_19") (pintype "passive"))
      (node (ref "U10") (pin "26") (pinfunction "VDD_26") (pintype "passive"))
      (node (ref "U10") (pin "35") (pinfunction "VUSB3V3_35") (pintype "passive"))
      (node (ref "U10") (pin "38") (pinfunction "VDD_38") (pintype "passive"))
      (node (ref "U10") (pin "57") (pinfunction "VDD_57") (pintype "passive"))
      (node (ref "U6") (pin "1") (pinfunction "OUT_1") (pintype "passive"))
    )
    (net (code "5") (name "/5.0V") (class "Default")
      (node (ref "C12") (pin "1") (pinfunction "1_1") (pintype "passive"))
      (node (ref "J3") (pin "1") (pinfunction "1_1") (pintype "passive"))
      (node (ref "R12") (pin "1") (pinfunction "1_1") (pintype "passive"))
      (node (ref "U7") (pin "3") (pinfunction "Vout_3") (pintype "passive"))
    )
    (net (code "6") (name "/12V") (class "Default")
      (node (ref "D28") (pin "1") (pinfunction "C_1") (pintype "passive"))
      (node (ref "D8") (pin "2") (pinfunction "A_2") (pintype "passive"))
      (node (ref "J12") (pin "1") (pinfunction "1_1") (pintype "passive"))
      (node (ref "J12") (pin "2") (pinfunction "2_2") (pintype "passive"))
      (node (ref "J12") (pin "3") (pinfunction "3_3") (pintype "passive"))
      (node (ref "J3") (pin "3") (pinfunction "3_3") (pintype "passive"))
      (node (ref "R13") (pin "2") (pinfunction "2_2") (pintype "passive"))
      (node (ref "R4") (pin "1") (pinfunction "1_1") (pintype "passive"))
    )
    (net (code "7") (name "/D+") (class "Default")
      (node (ref "D6") (pin "1") (pinfunction "1_1") (pintype "passive"))
      (node (ref "J2") (pin "3") (pinfunction "3_3") (pintype "passive"))
      (node (ref "U10") (pin "37") (pinfunction "D+/RG2_37") (pintype "passive"))
    )
    (net (code "8") (name "/D-") (class "Default")
      (node (ref "D6") (pin "3") (pinfunction "3_3") (pintype "passive"))
      (node (ref "J2") (pin "2") (pinfunction "2_2") (pintype "passive"))
      (node (ref "U10") (pin "36") (pinfunction "D-/RG3_36") (pintype "passive"))
    )
    (net (code "9") (name "/FB") (class "Default")
      (node (ref "C3") (pin "1") (pinfunction "1_1") (pintype "passive"))
      (node (ref "R6") (pin "1") (pinfunction "1_1") (pintype "passive"))
      (node (ref "U10") (pin "17") (pinfunction "PGEC1/AN6/RPI38/RB6_17") (pintype "passive"))
    )
    (net (code "10") (name "/GREEN") (class "Default")
      (node (ref "D2") (pin "2") (pinfunction "A_2") (pintype "passive"))
      (node (ref "U10") (pin "47") (pinfunction "PGED2/SOSCI/C3IN3-/RPI61/RC13_47") (pintype "passive"))
    )
    (net (code "11") (name "/LDO3.3V-5.0V") (class "Default")
      (node (ref "R14") (pin "1") (pinfunction "1_1") (pintype "passive"))
      (node (ref "U29") (pin "5") (pinfunction "CTL_5") (pintype "passive"))
      (node (ref "U29") (pin "8") (pinfunction "VCC_8") (pintype "passive"))
      (node (ref "U9") (pin "5") (pinfunction "CTL_5") (pintype "passive"))
      (node (ref "U9") (pin "8") (pinfunction "VCC_8") (pintype "passive"))
    )
    (net (code "12") (name "/LDO5.0V") (class "Default")
      (node (ref "C15") (pin "1") (pinfunction "1_1") (pintype "passive"))
      (node (ref "R11") (pin "1") (pinfunction "1_1") (pintype "passive"))
      (node (ref "R12") (pin "2") (pinfunction "2_2") (pintype "passive"))
      (node (ref "U6") (pin "5") (pinfunction "CTL_5") (pintype "passive"))
      (node (ref "U6") (pin "8") (pinfunction "VCC_8") (pintype "passive"))
    )
    (net (code "13") (name "/LM12V") (class "Default")
      (node (ref "D8") (pin "1") (pinfunction "C_1") (pintype "passive"))
      (node (ref "R13") (pin "1") (pinfunction "1_1") (pintype "passive"))
      (node (ref "U7") (pin "1") (pinfunction "Vin_1") (pintype "passive"))
    )
    (net (code "14") (name "/MCLR") (class "Default")
      (node (ref "C5") (pin "1") (pinfunction "1_1") (pintype "passive"))
      (node (ref "J1") (pin "1") (pinfunction "1_1") (pintype "passive"))
      (node (ref "R1") (pin "1") (pinfunction "1_1") (pintype "passive"))
      (node (ref "U10") (pin "7") (pinfunction "~{MCLR}_7") (pintype "passive"))
    )
    (net (code "15") (name "/MCU5.0V") (class "Default")
      (node (ref "R10") (pin "2") (pinfunction "2_2") (pintype "passive"))
      (node (ref "U10") (pin "34") (pinfunction "VBUS_34") (pintype "passive"))
    )
    (net (code "16") (name "/MEAS12") (class "Default")
      (node (ref "R4") (pin "2") (pinfunction "2_2") (pintype "passive"))
      (node (ref "R5") (pin "2") (pinfunction "2_2") (pintype "passive"))
      (node (ref "U10") (pin "18") (pinfunction "PGED1/AN7/RCV/RPI39/RB7_18") (pintype "passive"))
    )
    (net (code "17") (name "/Main OSC In") (class "Default")
      (node (ref "C10") (pin "1") (pinfunction "1_1") (pintype "passive"))
      (node (ref "U10") (pin "39") (pinfunction "OSC1/RPI60/RC12_39") (pintype "passive"))
      (node (ref "Y1") (pin "1") (pinfunction "1_1") (pintype "passive"))
    )
    (net (code "18") (name "/Main OSC Out") (class "Default")
      (node (ref "C11") (pin "1") (pinfunction "1_1") (pintype "passive"))
      (node (ref "U10") (pin "40") (pinfunction "OSC2/CLKO/RC15_40") (pintype "passive"))
      (node (ref "Y1") (pin "2") (pinfunction "2_2") (pintype "passive"))
    )
    (net (code "19") (name "/ORANGE") (class "Default")
      (node (ref "D4") (pin "2") (pinfunction "A_2") (pintype "passive"))
      (node (ref "U10") (pin "45") (pinfunction "PMCS1/RPI75/RD11_45") (pintype "passive"))
    )
    (net (code "20") (name "/PGC") (class "Default")
      (node (ref "J1") (pin "5") (pinfunction "5_5") (pintype "passive"))
      (node (ref "U10") (pin "15") (pinfunction "PGEC3/AN1/VREF-/RPI33/RB1_15") (pintype "passive"))
    )
    (net (code "21") (name "/PGD") (class "Default")
      (node (ref "J1") (pin "4") (pinfunction "4_4") (pintype "passive"))
      (node (ref "U10") (pin "16") (pinfunction "PGED3/AN0/VREF+/RPI32/RB0_16") (pintype "passive"))
    )
    (net (code "22") (name "/PWM1L") (class "Default")
      (node (ref "U10") (pin "60") (pinfunction "AN24/PWM1L/PMD0/RP80/RE0_60") (pintype "passive"))
    )
    (net (code "23") (name "/PWM2L") (class "Default")
      (node (ref "U10") (pin "62") (pinfunction "AN26/PWM2L/PMD2/RP82/RE2_62") (pintype "passive"))
    )
    (net (code "24") (name "/PWM3H") (class "Default")
      (node (ref "U10") (pin "1") (pinfunction "AN29/PWM3H/PMD5/RP85/RE5_1") (pintype "passive"))
    )
    (net (code "25") (name "/PWM4H") (class "Default")
      (node (ref "U10") (pin "3") (pinfunction "AN31/PWM4H/PMD7/RP87/RE7_3") (pintype "passive"))
    )
    (net (code "26") (name "/RED") (class "Default")
      (node (ref "D1") (pin "2") (pinfunction "A_2") (pintype "passive"))
      (node (ref "U10") (pin "48") (pinfunction "PGEC2/SOSCO/C3IN1-/T1CK/RPI62/RC14_48") (pintype "passive"))
    )
    (net (code "27") (name "/RESET_COLD_L") (class "Default")
      (node (ref "R21") (pin "1") (pinfunction "1_1") (pintype "passive"))
      (node (ref "R29") (pin "1") (pinfunction "1_1") (pintype "passive"))
    )
    (net (code "28") (name "/RESET_pic") (class "Default")
      (node (ref "R21") (pin "2") (pinfunction "2_2") (pintype "passive"))
      (node (ref "U10") (pin "8") (pinfunction "C2IN1-/PMA2/RPI121/RG9_8") (pintype "passive"))
    )
    (net (code "29") (name "/SER_CLK") (class "Default")
      (node (ref "R7") (pin "1") (pinfunction "1_1") (pintype "passive"))
      (node (ref "R8") (pin "1") (pinfunction "1_1") (pintype "passive"))
    )
    (net (code "30") (name "/SER_CLK_pic") (class "Default")
      (node (ref "R7") (pin "2") (pinfunction "2_2") (pintype "passive"))
      (node (ref "U10") (pin "4") (pinfunction "C1IN3-/SCK2/PMA5/RP118/RG6_4") (pintype "passive"))
    )
    (net (code "31") (name "/THDN") (class "Default")
      (node (ref "R9") (pin "1") (pinfunction "1_1") (pintype "passive"))
      (node (ref "U10") (pin "46") (pinfunction "INT0/DMH/RP64/RD0_46") (pintype "passive"))
    )
    (net (code "32") (name "/TXD_0") (class "Default")
      (node (ref "R20") (pin "2") (pinfunction "2_2") (pintype "passive"))
      (node (ref "U10") (pin "6") (pinfunction "C2IN3-/SDO2/PMA3/RP120/RG8_6") (pintype "passive"))
    )
    (net (code "33") (name "/TXD_1") (class "Default")
      (node (ref "R20") (pin "1") (pinfunction "1_1") (pintype "passive"))
      (node (ref "R22") (pin "1") (pinfunction "1_1") (pintype "passive"))
    )
    (net (code "34") (name "/TXD_2") (class "Default")
      (node (ref "Q51") (pin "1") (pinfunction "G_1") (pintype "passive"))
    )
    (net (code "35") (name "/TXD_10") (class "Default")
      (node (ref "Q51") (pin "3") (pinfunction "D_3") (pintype "passive"))
      (node (ref "R18") (pin "2") (pinfunction "2_2") (pintype "passive"))
      (node (ref "U10") (pin "5") (pinfunction "C1IN1-/SDI2/PMA4/RPI119/RG7_5") (pintype "passive"))
    )
    (net (code "36") (name "/USB5.0V") (class "Default")
      (node (ref "D6") (pin "4") (pinfunction "4_4") (pintype "passive"))
      (node (ref "D6") (pin "6") (pinfunction "6_6") (pintype "passive"))
      (node (ref "J2") (pin "1") (pinfunction "1_1") (pintype "passive"))
      (node (ref "R10") (pin "1") (pinfunction "1_1") (pintype "passive"))
      (node (ref "R11") (pin "2") (pinfunction "2_2") (pintype "passive"))
    )
    (net (code "37") (name "/VCAP") (class "Default")
      (node (ref "C2") (pin "1") (pinfunction "1_1") (pintype "passive"))
      (node (ref "U10") (pin "56") (pinfunction "VCAP_56") (pintype "passive"))
    )
    (net (code "38") (name "/YELLOW") (class "Default")
      (node (ref "D3") (pin "2") (pinfunction "A_2") (pintype "passive"))
      (node (ref "U10") (pin "44") (pinfunction "ASCL1/PMCS2/RPI74/RD10_44") (pintype "passive"))
    )
    (net (code "39") (name "GND") (class "Default")
      (node (ref "C10") (pin "2") (pinfunction "2_2") (pintype "passive"))
      (node (ref "C11") (pin "2") (pinfunction "2_2") (pintype "passive"))
      (node (ref "C12") (pin "2") (pinfunction "2_2") (pintype "passive"))
      (node (ref "C13") (pin "1") (pinfunction "1_1") (pintype "passive"))
      (node (ref "C14") (pin "2") (pinfunction "2_2") (pintype "passive"))
      (node (ref "C15") (pin "2") (pinfunction "2_2") (pintype "passive"))
      (node (ref "C16") (pin "2") (pinfunction "2_2") (pintype "passive"))
      (node (ref "C17") (pin "2") (pinfunction "2_2") (pintype "passive"))
      (node (ref "C2") (pin "2") (pinfunction "2_2") (pintype "passive"))
      (node (ref "C231") (pin "2") (pinfunction "2_2") (pintype "passive"))
      (node (ref "C232") (pin "2") (pinfunction "2_2") (pintype "passive"))
      (node (ref "C3") (pin "2") (pinfunction "2_2") (pintype "passive"))
      (node (ref "C347") (pin "2") (pinfunction "2_2") (pintype "passive"))
      (node (ref "C4") (pin "2") (pinfunction "2_2") (pintype "passive"))
      (node (ref "C5") (pin "2") (pinfunction "2_2") (pintype "passive"))
      (node (ref "C6") (pin "2") (pinfunction "2_2") (pintype "passive"))
      (node (ref "C7") (pin "2") (pinfunction "2_2") (pintype "passive"))
      (node (ref "C8") (pin "2") (pinfunction "2_2") (pintype "passive"))
      (node (ref "C9") (pin "2") (pinfunction "2_2") (pintype "passive"))
      (node (ref "D1") (pin "1") (pinfunction "C_1") (pintype "passive"))
      (node (ref "D2") (pin "1") (pinfunction "C_1") (pintype "passive"))
      (node (ref "D28") (pin "2") (pinfunction "A_2") (pintype "passive"))
      (node (ref "D3") (pin "1") (pinfunction "C_1") (pintype "passive"))
      (node (ref "D4") (pin "1") (pinfunction "C_1") (pintype "passive"))
      (node (ref "D6") (pin "2") (pinfunction "2_2") (pintype "passive"))
      (node (ref "D6") (pin "5") (pinfunction "5_5") (pintype "passive"))
      (node (ref "J1") (pin "3") (pinfunction "3_3") (pintype "passive"))
      (node (ref "J12") (pin "4") (pinfunction "4_4") (pintype "passive"))
      (node (ref "J12") (pin "5") (pinfunction "5_5") (pintype "passive"))
      (node (ref "J12") (pin "6") (pinfunction "6_6") (pintype "passive"))
      (node (ref "J13") (pin "1") (pinfunction "1_1") (pintype "passive"))
      (node (ref "J14") (pin "1") (pinfunction "1_1") (pintype "passive"))
      (node (ref "J15") (pin "1") (pinfunction "1_1") (pintype "passive"))
      (node (ref "J2") (pin "5") (pinfunction "5_5") (pintype "passive"))
      (node (ref "J2") (pin "6") (pinfunction "6_6") (pintype "passive"))
      (node (ref "J2") (pin "7") (pinfunction "7_7") (pintype "passive"))
      (node (ref "J2") (pin "8") (pinfunction "8_8") (pintype "passive"))
      (node (ref "J2") (pin "9") (pinfunction "9_9") (pintype "passive"))
      (node (ref "J22") (pin "1") (pinfunction "1_1") (pintype "passive"))
      (node (ref "J23") (pin "1") (pinfunction "1_1") (pintype "passive"))
      (node (ref "J24") (pin "1") (pinfunction "1_1") (pintype "passive"))
      (node (ref "J3") (pin "2") (pinfunction "2_2") (pintype "passive"))
      (node (ref "J9") (pin "1") (pinfunction "1_1") (pintype "passive"))
      (node (ref "Q51") (pin "2") (pinfunction "S_2") (pintype "passive"))
      (node (ref "R22") (pin "2") (pinfunction "2_2") (pintype "passive"))
      (node (ref "R28") (pin "2") (pinfunction "2_2") (pintype "passive"))
      (node (ref "R29") (pin "2") (pinfunction "2_2") (pintype "passive"))
      (node (ref "R5") (pin "1") (pinfunction "1_1") (pintype "passive"))
      (node (ref "R8") (pin "2") (pinfunction "2_2") (pintype "passive"))
      (node (ref "U10") (pin "20") (pinfunction "AVSS_20") (pintype "passive"))
      (node (ref "U10") (pin "25") (pinfunction "VSS_25") (pintype "passive"))
      (node (ref "U10") (pin "41") (pinfunction "VSS_41") (pintype "passive"))
      (node (ref "U10") (pin "9") (pinfunction "VSS_9") (pintype "passive"))
      (node (ref "U29") (pin "6") (pinfunction "GND_6") (pintype "passive"))
      (node (ref "U29") (pin "7") (pinfunction "GND_7") (pintype "passive"))
      (node (ref "U6") (pin "6") (pinfunction "GND_6") (pintype "passive"))
      (node (ref "U6") (pin "7") (pinfunction "GND_7") (pintype "passive"))
      (node (ref "U7") (pin "4") (pinfunction "GND_4") (pintype "passive"))
      (node (ref "U9") (pin "6") (pinfunction "GND_6") (pintype "passive"))
      (node (ref "U9") (pin "7") (pinfunction "GND_7") (pintype "passive"))
    )
    (net (code "40") (name "Net-(U10-AN2{slash}C2IN2-{slash}VMIO{slash}RPI34{slash}RB2)") (class "Default")
      (node (ref "TP7") (pin "1") (pinfunction "1_1") (pintype "passive"))
      (node (ref "U10") (pin "14") (pinfunction "AN2/C2IN2-/VMIO/RPI34/RB2_14") (pintype "passive"))
    )
    (net (code "41") (name "Net-(U10-AN3{slash}C2IN1+{slash}VPIO{slash}RPI35{slash}RB3)") (class "Default")
      (node (ref "TP6") (pin "1") (pinfunction "1_1") (pintype "passive"))
      (node (ref "U10") (pin "13") (pinfunction "AN3/C2IN1+/VPIO/RPI35/RB3_13") (pintype "passive"))
    )
    (net (code "42") (name "Net-(U10-AN4{slash}C1IN2-{slash}USBOEN{slash}RPI36{slash}RB4)") (class "Default")
      (node (ref "TP5") (pin "1") (pinfunction "1_1") (pintype "passive"))
      (node (ref "U10") (pin "12") (pinfunction "AN4/C1IN2-/USBOEN/RPI36/RB4_12") (pintype "passive"))
    )
    (net (code "43") (name "Net-(U10-AN5{slash}C1IN1+{slash}VBUSON{slash}VBUSST{slash}RPI37{slash}RB5)") (class "Default")
      (node (ref "TP3") (pin "1") (pinfunction "1_1") (pintype "passive"))
      (node (ref "U10") (pin "11") (pinfunction "AN5/C1IN1+/VBUSON/VBUSST/RPI37/RB5_11") (pintype "passive"))
    )
    (net (code "44") (name "Net-(U10-AN8{slash}PMA6{slash}RPI40{slash}RB8)") (class "Default")
      (node (ref "TP10") (pin "1") (pinfunction "1_1") (pintype "passive"))
      (node (ref "U10") (pin "21") (pinfunction "AN8/PMA6/RPI40/RB8_21") (pintype "passive"))
    )
    (net (code "45") (name "Net-(U10-AN9{slash}PMA7{slash}{slash}RPI41{slash}RB9)") (class "Default")
      (node (ref "TP11") (pin "1") (pinfunction "1_1") (pintype "passive"))
      (node (ref "U10") (pin "22") (pinfunction "AN9/PMA7//RPI41/RB9_22") (pintype "passive"))
    )
    (net (code "46") (name "Net-(U10-AN14{slash}PMA1{slash}RPI46{slash}RB14)") (class "Default")
      (node (ref "TP124") (pin "1") (pinfunction "1_1") (pintype "passive"))
      (node (ref "U10") (pin "29") (pinfunction "AN14/PMA1/RPI46/RB14_29") (pintype "passive"))
    )
    (net (code "47") (name "Net-(U10-AN15{slash}PMA0{slash}RPI47{slash}RB15)") (class "Default")
      (node (ref "TP125") (pin "1") (pinfunction "1_1") (pintype "passive"))
      (node (ref "U10") (pin "30") (pinfunction "AN15/PMA0/RPI47/RB15_30") (pintype "passive"))
    )
    (net (code "48") (name "Net-(U10-ASDA1{slash}DPLN{slash}RPI73{slash}RD9)") (class "Default")
      (node (ref "TP12") (pin "1") (pinfunction "1_1") (pintype "passive"))
      (node (ref "U10") (pin "43") (pinfunction "ASDA1/DPLN/RPI73/RD9_43") (pintype "passive"))
    )
    (net (code "49") (name "Net-(U10-C3IN1+{slash}VCMPST3{slash}RP71{slash}RD7)") (class "Default")
      (node (ref "TP18") (pin "1") (pinfunction "1_1") (pintype "passive"))
      (node (ref "U10") (pin "55") (pinfunction "C3IN1+/VCMPST3/RP71/RD7_55") (pintype "passive"))
    )
    (net (code "50") (name "Net-(U10-C3IN2-{slash}RP70{slash}RD6)") (class "Default")
      (node (ref "TP19") (pin "1") (pinfunction "1_1") (pintype "passive"))
      (node (ref "U10") (pin "54") (pinfunction "C3IN2-/RP70/RD6_54") (pintype "passive"))
    )
    (net (code "51") (name "Net-(U10-DPH{slash}RP66{slash}RD2)") (class "Default")
      (node (ref "TP22") (pin "1") (pinfunction "1_1") (pintype "passive"))
      (node (ref "U10") (pin "50") (pinfunction "DPH/RP66/RD2_50") (pintype "passive"))
    )
    (net (code "52") (name "Net-(U10-PMBE{slash}RP67{slash}RD3)") (class "Default")
      (node (ref "TP20") (pin "1") (pinfunction "1_1") (pintype "passive"))
      (node (ref "U10") (pin "51") (pinfunction "PMBE/RP67/RD3_51") (pintype "passive"))
    )
    (net (code "53") (name "Net-(U10-PMRD{slash}RP69{slash}RD5)") (class "Default")
      (node (ref "TP25") (pin "1") (pinfunction "1_1") (pintype "passive"))
      (node (ref "U10") (pin "53") (pinfunction "PMRD/RP69/RD5_53") (pintype "passive"))
    )
    (net (code "54") (name "Net-(U10-RTCC{slash}DMLN{slash}RPI72{slash}RD8)") (class "Default")
      (node (ref "TP13") (pin "1") (pinfunction "1_1") (pintype "passive"))
      (node (ref "U10") (pin "42") (pinfunction "RTCC/DMLN/RPI72/RD8_42") (pintype "passive"))
    )
    (net (code "55") (name "Net-(U10-SCL2{slash}PMA8{slash}RP101{slash}RF5)") (class "Default")
      (node (ref "TP127") (pin "1") (pinfunction "1_1") (pintype "passive"))
      (node (ref "U10") (pin "32") (pinfunction "SCL2/PMA8/RP101/RF5_32") (pintype "passive"))
    )
    (net (code "56") (name "Net-(U10-SDA2{slash}PMA9{slash}RP100{slash}RF4)") (class "Default")
      (node (ref "TP126") (pin "1") (pinfunction "1_1") (pintype "passive"))
      (node (ref "U10") (pin "31") (pinfunction "SDA2/PMA9/RP100/RF4_31") (pintype "passive"))
    )
    (net (code "57") (name "Net-(U10-TCK{slash}AN12{slash}PMA11{slash}RPI44{slash}RB12)") (class "Default")
      (node (ref "TP2") (pin "1") (pinfunction "1_1") (pintype "passive"))
      (node (ref "U10") (pin "27") (pinfunction "TCK/AN12/PMA11/RPI44/RB12_27") (pintype "passive"))
    )
    (net (code "58") (name "Net-(U10-TDI{slash}AN13{slash}PMA10{slash}RPI45{slash}RB13)") (class "Default")
      (node (ref "TP123") (pin "1") (pinfunction "1_1") (pintype "passive"))
      (node (ref "U10") (pin "28") (pinfunction "TDI/AN13/PMA10/RPI45/RB13_28") (pintype "passive"))
    )
    (net (code "59") (name "Net-(U10-TDO{slash}AN11{slash}PMA12{slash}RPI43{slash}RB11)") (class "Default")
      (node (ref "TP132") (pin "1") (pinfunction "1_1") (pintype "passive"))
      (node (ref "U10") (pin "24") (pinfunction "TDO/AN11/PMA12/RPI43/RB11_24") (pintype "passive"))
    )
    (net (code "60") (name "Net-(U10-TMS{slash}AN10{slash}CVREF{slash}PMA13{slash}RPI42{slash}RB10)") (class "Default")
      (node (ref "TP131") (pin "1") (pinfunction "1_1") (pintype "passive"))
      (node (ref "U10") (pin "23") (pinfunction "TMS/AN10/CVREF/PMA13/RPI42/RB10_23") (pintype "passive"))
    )
    (net (code "61") (name "Net-(U10-USBID{slash}RP99{slash}RF3)") (class "Default")
      (node (ref "TP21") (pin "1") (pinfunction "1_1") (pintype "passive"))
      (node (ref "U10") (pin "33") (pinfunction "USBID/RP99/RF3_33") (pintype "passive"))
    )
    (net (code "62") (name "Net-(U10-VCMPST1{slash}RP96{slash}RF0)") (class "Default")
      (node (ref "TP129") (pin "1") (pinfunction "1_1") (pintype "passive"))
      (node (ref "U10") (pin "58") (pinfunction "VCMPST1/RP96/RF0_58") (pintype "passive"))
    )
    (net (code "63") (name "Net-(U10-VCMPST2{slash}RP97{slash}RF1)") (class "Default")
      (node (ref "TP128") (pin "1") (pinfunction "1_1") (pintype "passive"))
      (node (ref "U10") (pin "59") (pinfunction "VCMPST2/RP97/RF1_59") (pintype "passive"))
    )
    (net (code "64") (name "Net-(U10-VCPCON{slash}RP65{slash}RD1)") (class "Default")
      (node (ref "TP23") (pin "1") (pinfunction "1_1") (pintype "passive"))
      (node (ref "U10") (pin "49") (pinfunction "VCPCON/RP65/RD1_49") (pintype "passive"))
    )
    (net (code "65") (name "Net-(U29-ADJ)") (class "Default")
      (node (ref "R27") (pin "2") (pinfunction "2_2") (pintype "passive"))
      (node (ref "R28") (pin "1") (pinfunction "1_1") (pintype "passive"))
      (node (ref "U29") (pin "2") (pinfunction "ADJ_2") (pintype "passive"))
    )
    (net (code "66") (name "unconnected-(J2-Pad4)") (class "Default")
      (node (ref "J2") (pin "4") (pinfunction "4_4") (pintype "passive+no_connect"))
    )
    (net (code "67") (name "unconnected-(U6-NC-Pad2)") (class "Default")
      (node (ref "U6") (pin "2") (pinfunction "NC_2") (pintype "passive+no_connect"))
    )
    (net (code "68") (name "unconnected-(U6-NC-Pad3)") (class "Default")
      (node (ref "U6") (pin "3") (pinfunction "NC_3") (pintype "passive+no_connect"))
    )
    (net (code "69") (name "unconnected-(U6-NC-Pad4)") (class "Default")
      (node (ref "U6") (pin "4") (pinfunction "NC_4") (pintype "passive+no_connect"))
    )
    (net (code "70") (name "unconnected-(U9-ADJ-Pad2)") (class "Default")
      (node (ref "U9") (pin "2") (pinfunction "ADJ_2") (pintype "passive+no_connect"))
    )
    (net (code "71") (name "unconnected-(U9-NC-Pad3)") (class "Default")
      (node (ref "U9") (pin "3") (pinfunction "NC_3") (pintype "passive+no_connect"))
    )
    (net (code "72") (name "unconnected-(U9-NC-Pad4)") (class "Default")
      (node (ref "U9") (pin "4") (pinfunction "NC_4") (pintype "passive+no_connect"))
    )
    (net (code "73") (name "unconnected-(U10-AN25{slash}PWM1H{slash}PMD1{slash}RPI81{slash}RE1-Pad61)") (class "Default")
      (node (ref "U10") (pin "61") (pinfunction "AN25/PWM1H/PMD1/RPI81/RE1_61") (pintype "passive+no_connect"))
    )
    (net (code "74") (name "unconnected-(U10-AN27{slash}PWM2H{slash}PMD3{slash}RPI83{slash}RE3-Pad63)") (class "Default")
      (node (ref "U10") (pin "63") (pinfunction "AN27/PWM2H/PMD3/RPI83/RE3_63") (pintype "passive+no_connect"))
    )
    (net (code "75") (name "unconnected-(U10-AN28{slash}PWM3L{slash}PMD4{slash}RP84{slash}RE4-Pad64)") (class "Default")
      (node (ref "U10") (pin "64") (pinfunction "AN28/PWM3L/PMD4/RP84/RE4_64") (pintype "passive+no_connect"))
    )
    (net (code "76") (name "unconnected-(U10-AN30{slash}PWM4L{slash}PMD6{slash}RPI86{slash}RE6-Pad2)") (class "Default")
      (node (ref "U10") (pin "2") (pinfunction "AN30/PWM4L/PMD6/RPI86/RE6_2") (pintype "passive+no_connect"))
    )
    (net (code "77") (name "unconnected-(U10-PMWR{slash}RP68{slash}RD4-Pad52)") (class "Default")
      (node (ref "U10") (pin "52") (pinfunction "PMWR/RP68/RD4_52") (pintype "passive+no_connect"))
    )
    (net (code "78") (name "unconnected-(U29-NC-Pad3)") (class "Default")
      (node (ref "U29") (pin "3") (pinfunction "NC_3") (pintype "passive+no_connect"))
    )
    (net (code "79") (name "unconnected-(U29-NC-Pad4)") (class "Default")
      (node (ref "U29") (pin "4") (pinfunction "NC_4") (pintype "passive+no_connect"))
    )
  )
)
